# MachChoCaAn.net
KiCad netlist of a schematic drawn in Altium Designer
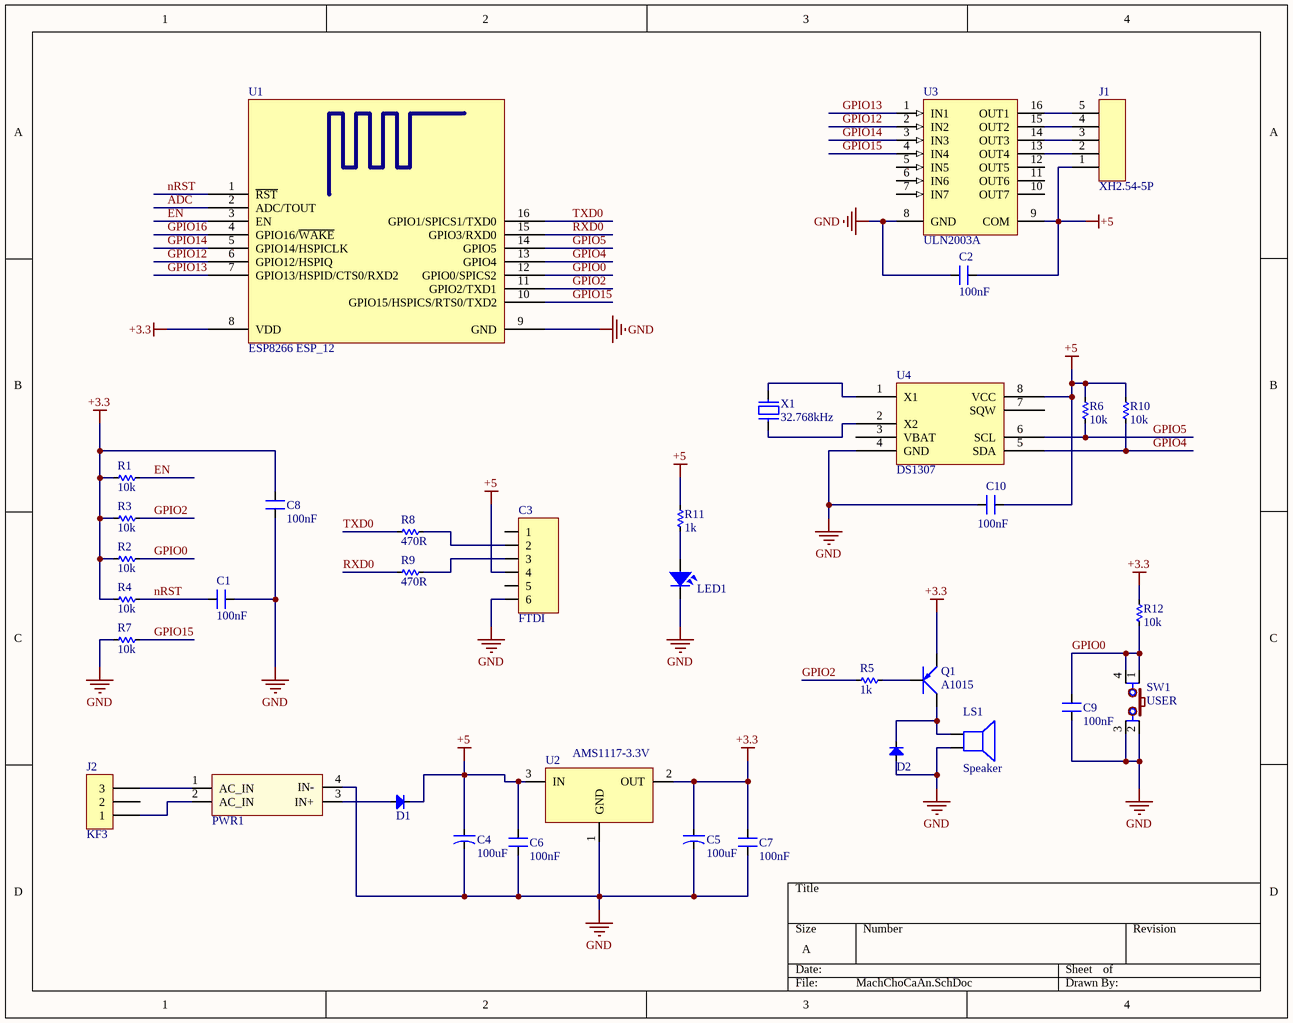
[diagram p0: MachChoCaAn.SchDoc]

(export (version "E")
  (design (tool "Eeschema 10.0.6"))
  (components
    (comp (ref "C1") (value "100nF") (footprint "CN-SMD-0805") (libsource (lib "LIBRARY") (part "CN")))
    (comp (ref "C2") (value "100nF") (footprint "CN-SMD-0805") (libsource (lib "LIBRARY") (part "CN")))
    (comp (ref "C3")
      (value "FTDI")
      (footprint "JP6-D1T")
      (description "WR-PHD 2.54 mm Angled Socket Header")
      (fields
        (field (name "MANUFACTURER") "Würth Elektronik eiSos GmbH")
        (field (name "PARTNO") "613006143121")
        (field (name "CREATED BY") "Karrer Zheng")
      )
      (libsource (lib "LIBRARY") (part "JP6"))
    )
    (comp (ref "C4")
      (value "100uF")
      (footprint "CA-ALU-6.3")
      (description "Capacitor (Semiconductor SIM Model)")
      (fields (field (name "PUBLISHER") "Altium Limited"))
      (libsource (lib "LIBRARY") (part "CN-ALU-DIP"))
    )
    (comp (ref "C5")
      (value "100uF")
      (footprint "CA-ALU-6.3")
      (description "Capacitor (Semiconductor SIM Model)")
      (fields (field (name "PUBLISHER") "Altium Limited"))
      (libsource (lib "LIBRARY") (part "CN-ALU-DIP"))
    )
    (comp (ref "C6") (value "100nF") (footprint "CN-SMD-0805") (libsource (lib "LIBRARY") (part "CN")))
    (comp (ref "C7") (value "100nF") (footprint "CN-SMD-0805") (libsource (lib "LIBRARY") (part "CN")))
    (comp (ref "C8") (value "100nF") (footprint "CN-SMD-0805") (libsource (lib "LIBRARY") (part "CN")))
    (comp (ref "C9") (value "100nF") (footprint "CN-SMD-0805") (libsource (lib "LIBRARY") (part "CN")))
    (comp (ref "C10") (value "100nF") (footprint "CN-SMD-0805") (libsource (lib "LIBRARY") (part "CN")))
    (comp (ref "D1")
      (value "Diode SMD")
      (footprint "DIO-SMD-106")
      (description "Default Diode")
      (fields (field (name "PUBLISHER") "Altium Limited"))
      (libsource (lib "LIBRARY") (part "Diode SMD"))
    )
    (comp (ref "D2")
      (value "Diode SMD")
      (footprint "DIO-SMD-106")
      (description "Default Diode")
      (fields (field (name "PUBLISHER") "Altium Limited"))
      (libsource (lib "LIBRARY") (part "Diode SMD"))
    )
    (comp (ref "J1") (value "XH2.54-5P") (footprint "XH2.54-5P") (libsource (lib "User") (part "XH2.54-5P")))
    (comp (ref "J2")
      (value "KF3")
      (footprint "KF3-5.08")
      (fields
        (field (name "MANUFACTURER") "Würth Elektronik eiSos GmbH")
        (field (name "PARTNO") "691103110003")
        (field (name "CREATED BY") "Karrer Zheng")
      )
      (libsource (lib "LIBRARY") (part "KF3"))
    )
    (comp (ref "LED1")
      (value "PWR")
      (footprint "LED-0805-Orange")
      (libsource (lib "LIBRARY") (part "LED SMD"))
    )
    (comp (ref "LS1")
      (value "Speaker")
      (footprint "SPEAKER")
      (description "Loudspeaker")
      (fields (field (name "PUBLISHER") "Altium Limited"))
      (libsource (lib "LIBRARY") (part "Speaker"))
    )
    (comp (ref "PWR1")
      (value "MINI_POWER")
      (footprint "MINI_POWER")
      (libsource (lib "User") (part "MINI_POWER"))
    )
    (comp (ref "Q1")
      (value "A1015")
      (footprint "SOT23B")
      (description "Dán")
      (libsource (lib "THU VIEN SCH_04042017_1") (part "A1015"))
    )
    (comp (ref "R1")
      (value "10k")
      (footprint "RES-SMD-0805")
      (description "Resistor")
      (fields
        (field (name "MANUFACTURER") "Generic Components")
        (field (name "PUBLISHER") "Altium Hobart Technology Centre")
      )
      (libsource (lib "LIBRARY") (part "Res-SMD"))
    )
    (comp (ref "R2")
      (value "10k")
      (footprint "RES-SMD-0805")
      (description "Resistor")
      (fields
        (field (name "MANUFACTURER") "Generic Components")
        (field (name "PUBLISHER") "Altium Hobart Technology Centre")
      )
      (libsource (lib "LIBRARY") (part "Res-SMD"))
    )
    (comp (ref "R3")
      (value "10k")
      (footprint "RES-SMD-0805")
      (description "Resistor")
      (fields
        (field (name "MANUFACTURER") "Generic Components")
        (field (name "PUBLISHER") "Altium Hobart Technology Centre")
      )
      (libsource (lib "LIBRARY") (part "Res-SMD"))
    )
    (comp (ref "R4")
      (value "10k")
      (footprint "RES-SMD-0805")
      (description "Resistor")
      (fields
        (field (name "MANUFACTURER") "Generic Components")
        (field (name "PUBLISHER") "Altium Hobart Technology Centre")
      )
      (libsource (lib "LIBRARY") (part "Res-SMD"))
    )
    (comp (ref "R5")
      (value "1k")
      (footprint "RES-SMD-0805")
      (description "Resistor")
      (fields
        (field (name "MANUFACTURER") "Generic Components")
        (field (name "PUBLISHER") "Altium Hobart Technology Centre")
      )
      (libsource (lib "LIBRARY") (part "Res-SMD"))
    )
    (comp (ref "R6")
      (value "10k")
      (footprint "RES-SMD-0805")
      (description "Resistor")
      (fields
        (field (name "MANUFACTURER") "Generic Components")
        (field (name "PUBLISHER") "Altium Hobart Technology Centre")
      )
      (libsource (lib "LIBRARY") (part "Res-SMD"))
    )
    (comp (ref "R7")
      (value "10k")
      (footprint "RES-SMD-0805")
      (description "Resistor")
      (fields
        (field (name "MANUFACTURER") "Generic Components")
        (field (name "PUBLISHER") "Altium Hobart Technology Centre")
      )
      (libsource (lib "LIBRARY") (part "Res-SMD"))
    )
    (comp (ref "R8")
      (value "470R")
      (footprint "RES-SMD-0805")
      (description "Resistor")
      (fields
        (field (name "MANUFACTURER") "Generic Components")
        (field (name "PUBLISHER") "Altium Hobart Technology Centre")
      )
      (libsource (lib "LIBRARY") (part "Res-SMD"))
    )
    (comp (ref "R9")
      (value "470R")
      (footprint "RES-SMD-0805")
      (description "Resistor")
      (fields
        (field (name "MANUFACTURER") "Generic Components")
        (field (name "PUBLISHER") "Altium Hobart Technology Centre")
      )
      (libsource (lib "LIBRARY") (part "Res-SMD"))
    )
    (comp (ref "R10")
      (value "10k")
      (footprint "RES-SMD-0805")
      (description "Resistor")
      (fields
        (field (name "MANUFACTURER") "Generic Components")
        (field (name "PUBLISHER") "Altium Hobart Technology Centre")
      )
      (libsource (lib "LIBRARY") (part "Res-SMD"))
    )
    (comp (ref "R11")
      (value "1k")
      (footprint "RES-SMD-0805")
      (description "Resistor")
      (fields
        (field (name "MANUFACTURER") "Generic Components")
        (field (name "PUBLISHER") "Altium Hobart Technology Centre")
      )
      (libsource (lib "LIBRARY") (part "Res-SMD"))
    )
    (comp (ref "R12")
      (value "10k")
      (footprint "RES-SMD-0805")
      (description "Resistor")
      (fields
        (field (name "MANUFACTURER") "Generic Components")
        (field (name "PUBLISHER") "Altium Hobart Technology Centre")
      )
      (libsource (lib "LIBRARY") (part "Res-SMD"))
    )
    (comp (ref "SW1")
      (value "USER")
      (footprint "SW2-DIP")
      (description "Switch button 4 pin")
      (libsource (lib "LIBRARY") (part "SW4"))
    )
    (comp (ref "U1")
      (value "ESP8266 ESP_12")
      (footprint "ESP8266 ESP_12")
      (description "ESP8266 ESP-12")
      (fields (field (name "PUBLISHER") "Cynetik Group") (field (name "LATESTREVIEWER") "Zion Blue"))
      (libsource (lib "ESP8266") (part "ESP8266 ESP_12"))
    )
    (comp (ref "U2")
      (value "AMS1117-3.3V")
      (footprint "SOT223")
      (description "800mA Low-Dropout Linear Regulator")
      (fields (field (name "CREATOR") "Nguyen Ba Bien"))
      (libsource (lib "LIBRARY") (part "LM1117"))
    )
    (comp (ref "U3")
      (value "ULN2003A")
      (footprint "SO16")
      (description "High-Voltage, High-Current Darlington Array")
      (fields (field (name "PUBLISHER") "Altium Limited"))
      (libsource (lib "LIBRARY") (part "ULN2003A"))
    )
    (comp (ref "U4") (value "DS1307") (footprint "DS1307") (libsource (lib "User") (part "DS1307")))
    (comp (ref "X1")
      (value "32.768kHz")
      (footprint "XT32k")
      (description "Crystal, 32.768 KHz, -40 to 85 degC, 3.2 x 1.5 x 0.9 mm SMD")
      (libsource (lib "LIBRARY") (part "XT2"))
    )
  )
  (nets
    (net (code "1") (name "+3.3") (class "Default")
      (node (ref "C5") (pin "1") (pinfunction "1_1") (pintype "passive"))
      (node (ref "C7") (pin "2") (pinfunction "2_2") (pintype "passive"))
      (node (ref "C8") (pin "2") (pinfunction "2_2") (pintype "passive"))
      (node (ref "Q1") (pin "3") (pinfunction "E_3") (pintype "passive"))
      (node (ref "R1") (pin "1") (pinfunction "1_1") (pintype "passive"))
      (node (ref "R12") (pin "2") (pinfunction "2_2") (pintype "passive"))
      (node (ref "R2") (pin "1") (pinfunction "1_1") (pintype "passive"))
      (node (ref "R3") (pin "1") (pinfunction "1_1") (pintype "passive"))
      (node (ref "R4") (pin "1") (pinfunction "1_1") (pintype "passive"))
      (node (ref "U1") (pin "8") (pinfunction "VDD_8") (pintype "passive"))
      (node (ref "U2") (pin "2") (pinfunction "OUT_2") (pintype "passive"))
    )
    (net (code "2") (name "+5") (class "Default")
      (node (ref "C10") (pin "2") (pinfunction "2_2") (pintype "passive"))
      (node (ref "C2") (pin "2") (pinfunction "2_2") (pintype "passive"))
      (node (ref "C3") (pin "4") (pinfunction "4_4") (pintype "passive"))
      (node (ref "C4") (pin "1") (pinfunction "1_1") (pintype "passive"))
      (node (ref "C6") (pin "2") (pinfunction "2_2") (pintype "passive"))
      (node (ref "D1") (pin "2") (pinfunction "K_2") (pintype "passive"))
      (node (ref "J1") (pin "1") (pinfunction "1_1") (pintype "passive"))
      (node (ref "R10") (pin "2") (pinfunction "2_2") (pintype "passive"))
      (node (ref "R11") (pin "1") (pinfunction "1_1") (pintype "passive"))
      (node (ref "R6") (pin "2") (pinfunction "2_2") (pintype "passive"))
      (node (ref "U2") (pin "3") (pinfunction "IN_3") (pintype "passive"))
      (node (ref "U3") (pin "9") (pinfunction "COM_9") (pintype "passive"))
      (node (ref "U4") (pin "8") (pinfunction "VCC_8") (pintype "passive"))
    )
    (net (code "3") (name "/ADC") (class "Default")
      (node (ref "U1") (pin "2") (pinfunction "ADC/TOUT_2") (pintype "passive"))
    )
    (net (code "4") (name "/EN") (class "Default")
      (node (ref "R1") (pin "2") (pinfunction "2_2") (pintype "passive"))
      (node (ref "U1") (pin "3") (pinfunction "EN_3") (pintype "passive"))
    )
    (net (code "5") (name "/GPIO0") (class "Default")
      (node (ref "C9") (pin "2") (pinfunction "2_2") (pintype "passive"))
      (node (ref "R12") (pin "1") (pinfunction "1_1") (pintype "passive"))
      (node (ref "R2") (pin "2") (pinfunction "2_2") (pintype "passive"))
      (node (ref "SW1") (pin "1") (pintype "passive"))
      (node (ref "SW1") (pin "4") (pinfunction "4_4") (pintype "passive"))
      (node (ref "U1") (pin "12") (pinfunction "GPIO0/SPICS2_12") (pintype "passive"))
    )
    (net (code "6") (name "/GPIO2") (class "Default")
      (node (ref "R3") (pin "2") (pinfunction "2_2") (pintype "passive"))
      (node (ref "R5") (pin "2") (pinfunction "2_2") (pintype "passive"))
      (node (ref "U1") (pin "11") (pinfunction "GPIO2/TXD1_11") (pintype "passive"))
    )
    (net (code "7") (name "/GPIO4") (class "Default")
      (node (ref "R10") (pin "1") (pinfunction "1_1") (pintype "passive"))
      (node (ref "U1") (pin "13") (pinfunction "GPIO4_13") (pintype "passive"))
      (node (ref "U4") (pin "5") (pinfunction "SDA_5") (pintype "passive"))
    )
    (net (code "8") (name "/GPIO5") (class "Default")
      (node (ref "R6") (pin "1") (pinfunction "1_1") (pintype "passive"))
      (node (ref "U1") (pin "14") (pinfunction "GPIO5_14") (pintype "passive"))
      (node (ref "U4") (pin "6") (pinfunction "SCL_6") (pintype "passive"))
    )
    (net (code "9") (name "/GPIO12") (class "Default")
      (node (ref "U1") (pin "6") (pinfunction "GPIO12/HSPIQ_6") (pintype "passive"))
      (node (ref "U3") (pin "2") (pinfunction "IN2_2") (pintype "input"))
    )
    (net (code "10") (name "/GPIO13") (class "Default")
      (node (ref "U1") (pin "7") (pinfunction "GPIO13/HSPID/CTS0/RXD2_7") (pintype "passive"))
      (node (ref "U3") (pin "1") (pinfunction "IN1_1") (pintype "input"))
    )
    (net (code "11") (name "/GPIO14") (class "Default")
      (node (ref "U1") (pin "5") (pinfunction "GPIO14/HSPICLK_5") (pintype "passive"))
      (node (ref "U3") (pin "3") (pinfunction "IN3_3") (pintype "input"))
    )
    (net (code "12") (name "/GPIO15") (class "Default")
      (node (ref "R7") (pin "2") (pinfunction "2_2") (pintype "passive"))
      (node (ref "U1") (pin "10") (pinfunction "GPIO15/HSPICS/RTS0/TXD2_10") (pintype "passive"))
      (node (ref "U3") (pin "4") (pinfunction "IN4_4") (pintype "input"))
    )
    (net (code "13") (name "/GPIO16") (class "Default")
      (node (ref "U1") (pin "4") (pinfunction "GPIO16/~{WAKE}_4") (pintype "passive"))
    )
    (net (code "14") (name "/RXD0") (class "Default")
      (node (ref "R9") (pin "1") (pinfunction "1_1") (pintype "passive"))
      (node (ref "U1") (pin "15") (pinfunction "GPIO3/RXD0_15") (pintype "passive"))
    )
    (net (code "15") (name "/TXD0") (class "Default")
      (node (ref "R8") (pin "1") (pinfunction "1_1") (pintype "passive"))
      (node (ref "U1") (pin "16") (pinfunction "GPIO1/SPICS1/TXD0_16") (pintype "passive"))
    )
    (net (code "16") (name "/nRST") (class "Default")
      (node (ref "C1") (pin "1") (pinfunction "1_1") (pintype "passive"))
      (node (ref "R4") (pin "2") (pinfunction "2_2") (pintype "passive"))
      (node (ref "U1") (pin "1") (pinfunction "~{RST}_1") (pintype "passive"))
    )
    (net (code "17") (name "GND") (class "Default")
      (node (ref "C1") (pin "2") (pinfunction "2_2") (pintype "passive"))
      (node (ref "C10") (pin "1") (pinfunction "1_1") (pintype "passive"))
      (node (ref "C2") (pin "1") (pinfunction "1_1") (pintype "passive"))
      (node (ref "C3") (pin "6") (pinfunction "6_6") (pintype "passive"))
      (node (ref "C4") (pin "2") (pinfunction "2_2") (pintype "passive"))
      (node (ref "C5") (pin "2") (pinfunction "2_2") (pintype "passive"))
      (node (ref "C6") (pin "1") (pinfunction "1_1") (pintype "passive"))
      (node (ref "C7") (pin "1") (pinfunction "1_1") (pintype "passive"))
      (node (ref "C8") (pin "1") (pinfunction "1_1") (pintype "passive"))
      (node (ref "C9") (pin "1") (pinfunction "1_1") (pintype "passive"))
      (node (ref "D2") (pin "1") (pinfunction "A_1") (pintype "passive"))
      (node (ref "LED1") (pin "2") (pinfunction "2_2") (pintype "passive"))
      (node (ref "LS1") (pin "2") (pinfunction "2_2") (pintype "passive"))
      (node (ref "PWR1") (pin "4") (pinfunction "IN-_4") (pintype "passive"))
      (node (ref "R7") (pin "1") (pinfunction "1_1") (pintype "passive"))
      (node (ref "SW1") (pin "2") (pinfunction "2_2") (pintype "passive"))
      (node (ref "SW1") (pin "3") (pinfunction "3_3") (pintype "passive"))
      (node (ref "U1") (pin "9") (pinfunction "GND_9") (pintype "passive"))
      (node (ref "U2") (pin "1") (pinfunction "GND_1") (pintype "passive"))
      (node (ref "U3") (pin "8") (pinfunction "GND_8") (pintype "power_in"))
      (node (ref "U4") (pin "4") (pinfunction "GND_4") (pintype "passive"))
    )
    (net (code "18") (name "Net-(C3-Pad2)") (class "Default")
      (node (ref "C3") (pin "2") (pinfunction "2_2") (pintype "passive"))
      (node (ref "R8") (pin "2") (pinfunction "2_2") (pintype "passive"))
    )
    (net (code "19") (name "Net-(C3-Pad3)") (class "Default")
      (node (ref "C3") (pin "3") (pinfunction "3_3") (pintype "passive"))
      (node (ref "R9") (pin "2") (pinfunction "2_2") (pintype "passive"))
    )
    (net (code "20") (name "Net-(D1-A)") (class "Default")
      (node (ref "D1") (pin "1") (pinfunction "A_1") (pintype "passive"))
      (node (ref "PWR1") (pin "3") (pinfunction "IN+_3") (pintype "passive"))
    )
    (net (code "21") (name "Net-(D2-K)") (class "Default")
      (node (ref "D2") (pin "2") (pinfunction "K_2") (pintype "passive"))
      (node (ref "LS1") (pin "1") (pinfunction "1_1") (pintype "passive"))
      (node (ref "Q1") (pin "2") (pinfunction "C_2") (pintype "passive"))
    )
    (net (code "22") (name "Net-(J2-Pad1)") (class "Default")
      (node (ref "J2") (pin "1") (pinfunction "1_1") (pintype "passive"))
      (node (ref "PWR1") (pin "2") (pinfunction "AC_IN_2") (pintype "passive"))
    )
    (net (code "23") (name "Net-(J2-Pad3)") (class "Default")
      (node (ref "J2") (pin "3") (pinfunction "3_3") (pintype "passive"))
      (node (ref "PWR1") (pin "1") (pinfunction "AC_IN_1") (pintype "passive"))
    )
    (net (code "24") (name "Net-(LED1-Pad1)") (class "Default")
      (node (ref "LED1") (pin "1") (pinfunction "1_1") (pintype "passive"))
      (node (ref "R11") (pin "2") (pinfunction "2_2") (pintype "passive"))
    )
    (net (code "25") (name "Net-(Q1-B)") (class "Default")
      (node (ref "Q1") (pin "1") (pinfunction "B_1") (pintype "passive"))
      (node (ref "R5") (pin "1") (pinfunction "1_1") (pintype "passive"))
    )
    (net (code "26") (name "Net-(U3-OUT1)") (class "Default")
      (node (ref "J1") (pin "5") (pinfunction "5_5") (pintype "passive"))
      (node (ref "U3") (pin "16") (pinfunction "OUT1_16") (pintype "open_collector"))
    )
    (net (code "27") (name "Net-(U3-OUT2)") (class "Default")
      (node (ref "J1") (pin "4") (pinfunction "4_4") (pintype "passive"))
      (node (ref "U3") (pin "15") (pinfunction "OUT2_15") (pintype "open_collector"))
    )
    (net (code "28") (name "Net-(U3-OUT3)") (class "Default")
      (node (ref "J1") (pin "3") (pinfunction "3_3") (pintype "passive"))
      (node (ref "U3") (pin "14") (pinfunction "OUT3_14") (pintype "open_collector"))
    )
    (net (code "29") (name "Net-(U3-OUT4)") (class "Default")
      (node (ref "J1") (pin "2") (pinfunction "2_2") (pintype "passive"))
      (node (ref "U3") (pin "13") (pinfunction "OUT4_13") (pintype "open_collector"))
    )
    (net (code "30") (name "Net-(U4-X1)") (class "Default")
      (node (ref "U4") (pin "1") (pinfunction "X1_1") (pintype "passive"))
      (node (ref "X1") (pin "2") (pinfunction "2_2") (pintype "passive"))
    )
    (net (code "31") (name "Net-(U4-X2)") (class "Default")
      (node (ref "U4") (pin "2") (pinfunction "X2_2") (pintype "passive"))
      (node (ref "X1") (pin "1") (pinfunction "1_1") (pintype "passive"))
    )
    (net (code "32") (name "unconnected-(C3-Pad1)") (class "Default")
      (node (ref "C3") (pin "1") (pinfunction "1_1") (pintype "passive"))
    )
    (net (code "33") (name "unconnected-(C3-Pad5)") (class "Default")
      (node (ref "C3") (pin "5") (pinfunction "5_5") (pintype "passive"))
    )
    (net (code "34") (name "unconnected-(J2-Pad2)") (class "Default")
      (node (ref "J2") (pin "2") (pinfunction "2_2") (pintype "passive"))
    )
    (net (code "35") (name "unconnected-(U3-IN5-Pad5)") (class "Default")
      (node (ref "U3") (pin "5") (pinfunction "IN5_5") (pintype "input"))
    )
    (net (code "36") (name "unconnected-(U3-IN6-Pad6)") (class "Default")
      (node (ref "U3") (pin "6") (pinfunction "IN6_6") (pintype "input"))
    )
    (net (code "37") (name "unconnected-(U3-IN7-Pad7)") (class "Default")
      (node (ref "U3") (pin "7") (pinfunction "IN7_7") (pintype "input"))
    )
    (net (code "38") (name "unconnected-(U3-OUT5-Pad12)") (class "Default")
      (node (ref "U3") (pin "12") (pinfunction "OUT5_12") (pintype "open_collector"))
    )
    (net (code "39") (name "unconnected-(U3-OUT6-Pad11)") (class "Default")
      (node (ref "U3") (pin "11") (pinfunction "OUT6_11") (pintype "open_collector"))
    )
    (net (code "40") (name "unconnected-(U3-OUT7-Pad10)") (class "Default")
      (node (ref "U3") (pin "10") (pinfunction "OUT7_10") (pintype "open_collector"))
    )
    (net (code "41") (name "unconnected-(U4-SQW-Pad7)") (class "Default")
      (node (ref "U4") (pin "7") (pinfunction "SQW_7") (pintype "passive"))
    )
    (net (code "42") (name "unconnected-(U4-VBAT-Pad3)") (class "Default")
      (node (ref "U4") (pin "3") (pinfunction "VBAT_3") (pintype "passive"))
    )
  )
)
